# fdcanusb.net
KiCad netlist of a schematic drawn in EAGLE
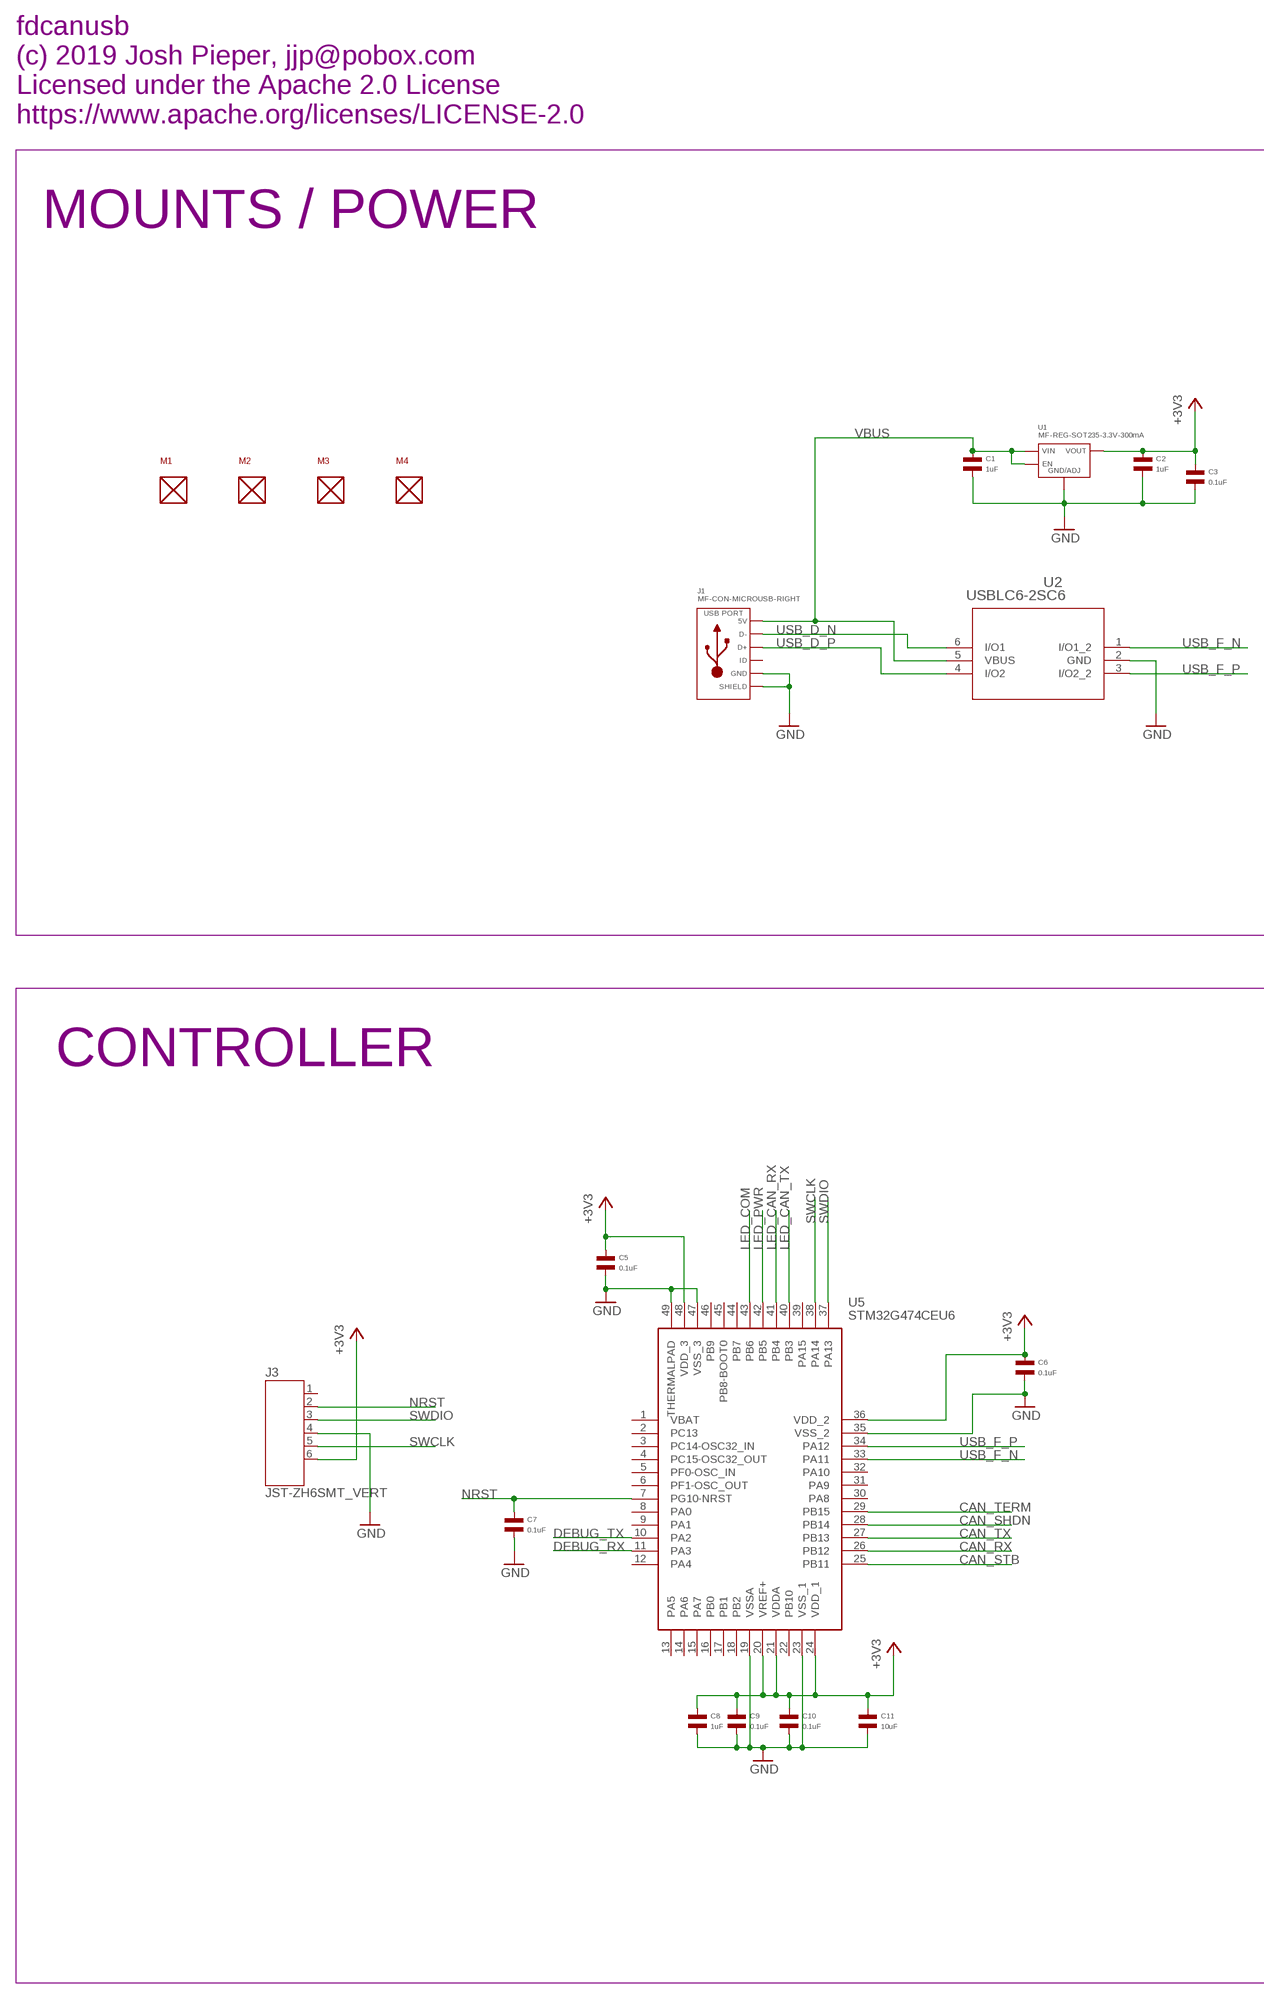
[diagram p0: schematic, sheet 1, part 1 of 2]
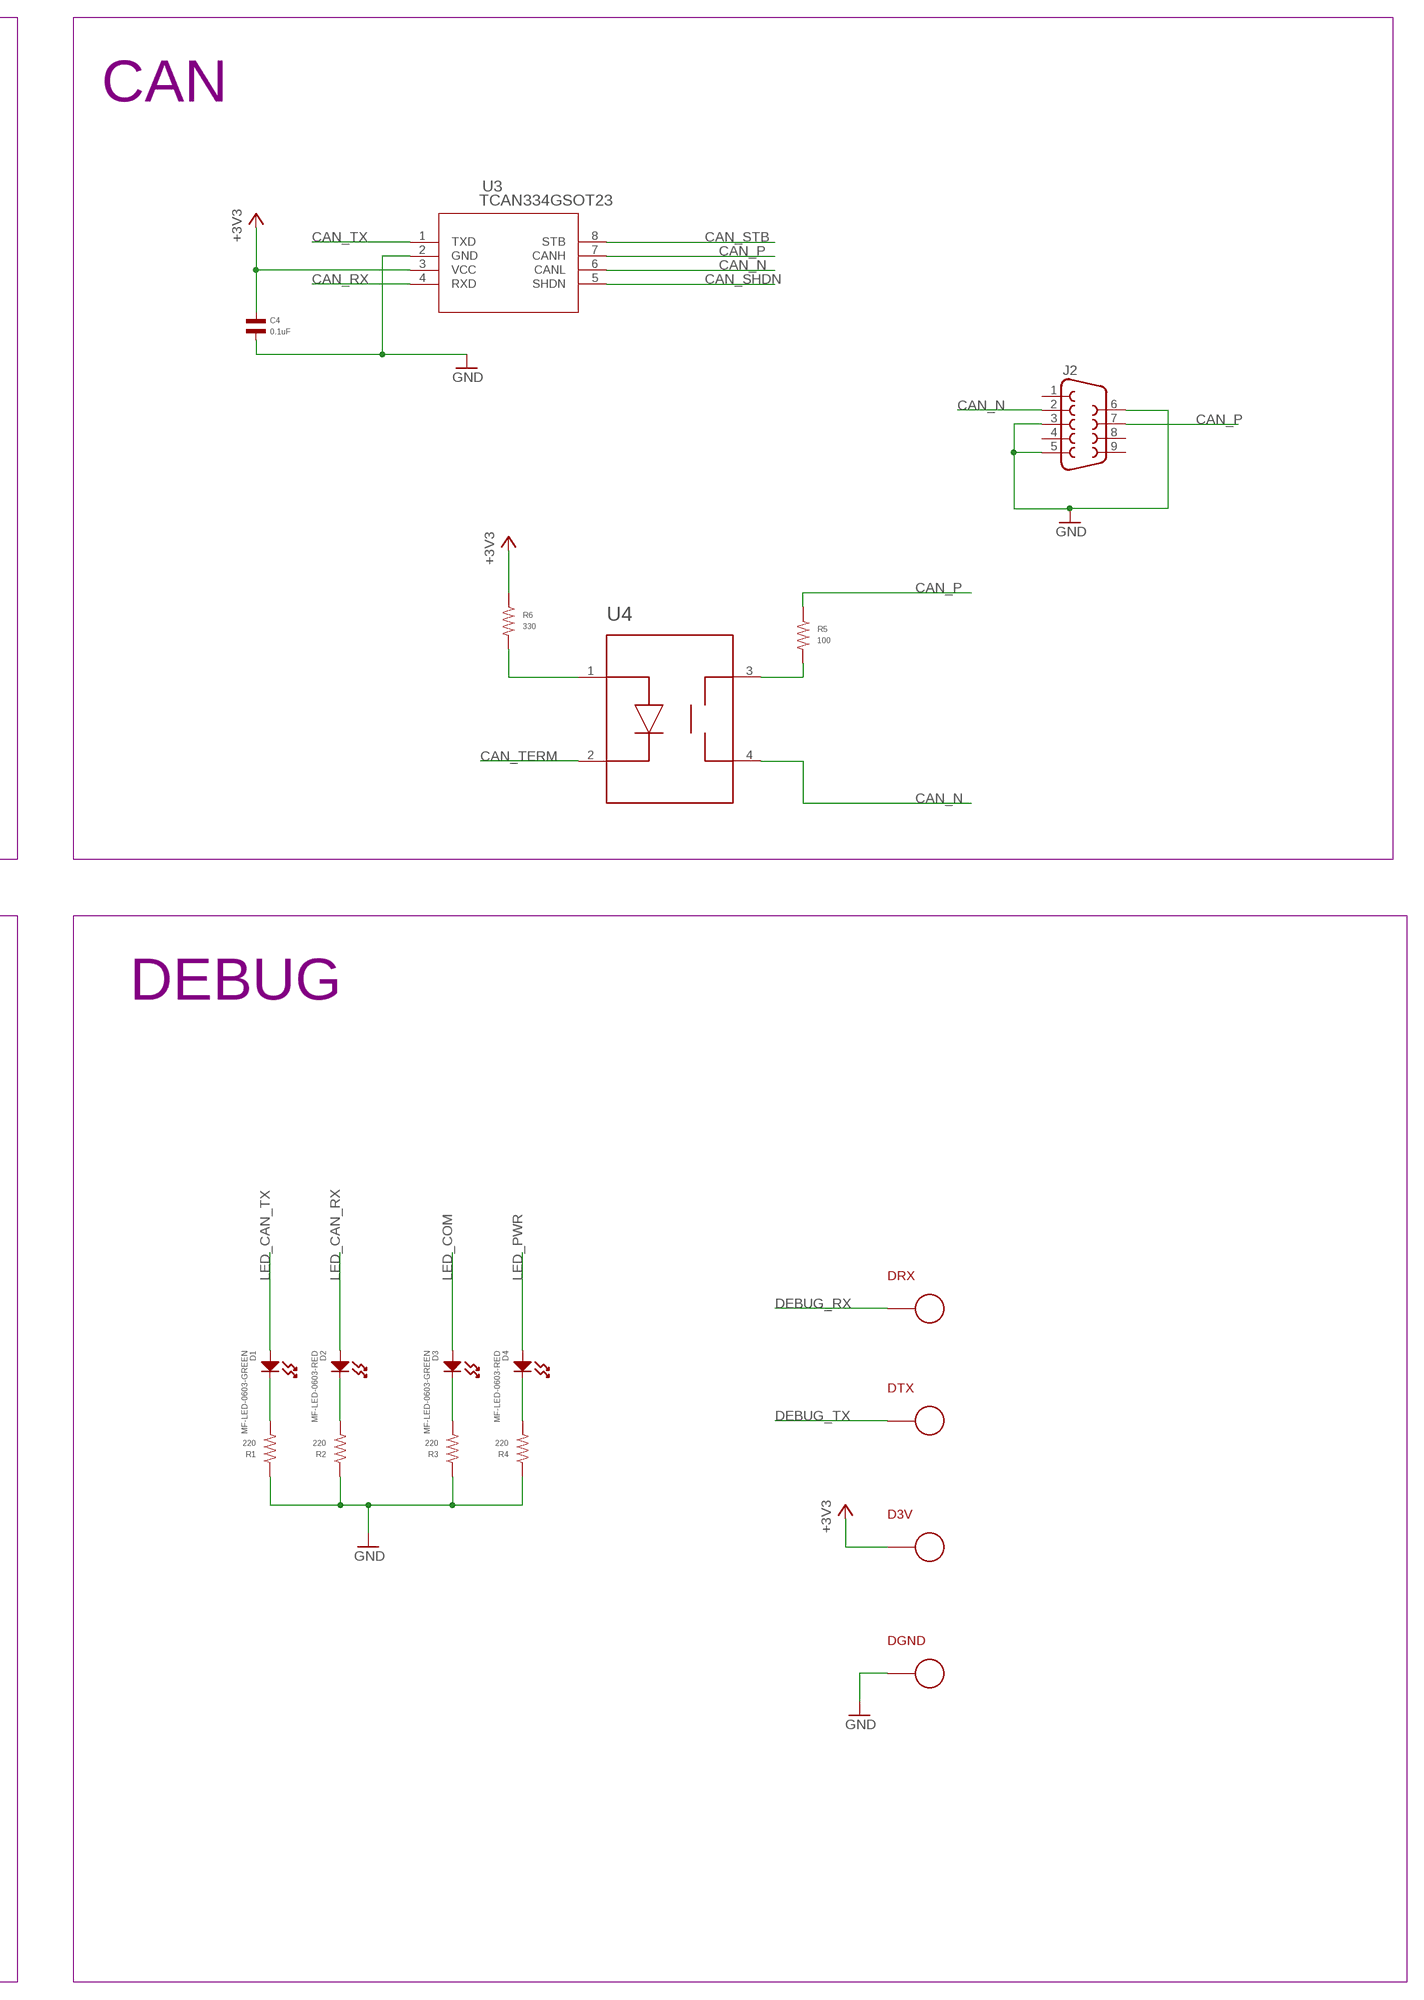
[diagram p1: schematic, sheet 1, part 2 of 2]

(export (version "E")
  (design (tool "Eeschema 10.0.6"))
  (components
    (comp (ref "C1")
      (value "1uF")
      (footprint "eagle-import:C0603")
      (fields (field (name "HOUSEPART") "YES") (field (name "MPN") "MF-CAP-0603-1uF"))
      (libsource (lib "eagle-import") (part "CAPACITOR_NP_0603"))
    )
    (comp (ref "C2")
      (value "1uF")
      (footprint "eagle-import:C0603")
      (fields (field (name "HOUSEPART") "YES") (field (name "MPN") "MF-CAP-0603-1uF"))
      (libsource (lib "eagle-import") (part "CAPACITOR_NP_0603"))
    )
    (comp (ref "C3")
      (value "0.1uF")
      (footprint "eagle-import:C0402")
      (fields (field (name "HOUSEPART") "YES") (field (name "MPN") "MF-CAP-0402-0.1uF"))
      (libsource (lib "eagle-import") (part "CAPACITOR_NP_0402"))
    )
    (comp (ref "C4")
      (value "0.1uF")
      (footprint "eagle-import:C0402")
      (fields (field (name "HOUSEPART") "YES") (field (name "MPN") "MF-CAP-0402-0.1uF"))
      (libsource (lib "eagle-import") (part "CAPACITOR_NP_0402"))
    )
    (comp (ref "C5")
      (value "0.1uF")
      (footprint "eagle-import:C0402")
      (fields (field (name "HOUSEPART") "YES") (field (name "MPN") "MF-CAP-0402-0.1uF"))
      (libsource (lib "eagle-import") (part "CAPACITOR_NP_0402"))
    )
    (comp (ref "C6")
      (value "0.1uF")
      (footprint "eagle-import:C0402")
      (fields (field (name "HOUSEPART") "YES") (field (name "MPN") "MF-CAP-0402-0.1uF"))
      (libsource (lib "eagle-import") (part "CAPACITOR_NP_0402"))
    )
    (comp (ref "C7")
      (value "0.1uF")
      (footprint "eagle-import:C0402")
      (fields (field (name "HOUSEPART") "YES") (field (name "MPN") "MF-CAP-0402-0.1uF"))
      (libsource (lib "eagle-import") (part "CAPACITOR_NP_0402"))
    )
    (comp (ref "C8")
      (value "1uF")
      (footprint "eagle-import:C0603")
      (fields (field (name "HOUSEPART") "YES") (field (name "MPN") "MF-CAP-0603-1uF"))
      (libsource (lib "eagle-import") (part "CAPACITOR_NP_0603"))
    )
    (comp (ref "C9")
      (value "0.1uF")
      (footprint "eagle-import:C0402")
      (fields (field (name "HOUSEPART") "YES") (field (name "MPN") "MF-CAP-0402-0.1uF"))
      (libsource (lib "eagle-import") (part "CAPACITOR_NP_0402"))
    )
    (comp (ref "C10")
      (value "0.1uF")
      (footprint "eagle-import:C0402")
      (fields (field (name "HOUSEPART") "YES") (field (name "MPN") "MF-CAP-0402-0.1uF"))
      (libsource (lib "eagle-import") (part "CAPACITOR_NP_0402"))
    )
    (comp (ref "C11")
      (value "10uF")
      (footprint "eagle-import:C1206")
      (fields (field (name "HOUSEPART") "YES") (field (name "MPN") "MF-CAP-1206-10uF"))
      (libsource (lib "eagle-import") (part "CAPACITOR_NP_1206"))
    )
    (comp (ref "D1")
      (value "MF-LED-0603-GREEN")
      (footprint "eagle-import:LED0603")
      (fields (field (name "HOUSEPART") "YES"))
      (libsource (lib "eagle-import") (part "LED_SINGLE-0603-GREEN"))
    )
    (comp (ref "D2")
      (value "MF-LED-0603-RED")
      (footprint "eagle-import:LED0603")
      (fields (field (name "HOUSEPART") "YES"))
      (libsource (lib "eagle-import") (part "LED_SINGLE-0603-RED"))
    )
    (comp (ref "D3")
      (value "MF-LED-0603-GREEN")
      (footprint "eagle-import:LED0603")
      (fields (field (name "HOUSEPART") "YES"))
      (libsource (lib "eagle-import") (part "LED_SINGLE-0603-GREEN"))
    )
    (comp (ref "D3V")
      (value "PAD24AWG_PAD")
      (footprint "eagle-import:24AWG_PAD")
      (libsource (lib "eagle-import") (part "PAD24AWG_PAD"))
    )
    (comp (ref "D4")
      (value "MF-LED-0603-RED")
      (footprint "eagle-import:LED0603")
      (fields (field (name "HOUSEPART") "YES"))
      (libsource (lib "eagle-import") (part "LED_SINGLE-0603-RED"))
    )
    (comp (ref "DGND")
      (value "PAD24AWG_PAD")
      (footprint "eagle-import:24AWG_PAD")
      (libsource (lib "eagle-import") (part "PAD24AWG_PAD"))
    )
    (comp (ref "DRX")
      (value "PAD24AWG_PAD")
      (footprint "eagle-import:24AWG_PAD")
      (libsource (lib "eagle-import") (part "PAD24AWG_PAD"))
    )
    (comp (ref "DTX")
      (value "PAD24AWG_PAD")
      (footprint "eagle-import:24AWG_PAD")
      (libsource (lib "eagle-import") (part "PAD24AWG_PAD"))
    )
    (comp (ref "J1")
      (value "MF-CON-MICROUSB-RIGHT")
      (footprint "eagle-import:MICROUSB-RIGHT")
      (fields (field (name "HOUSEPART") "YES"))
      (libsource (lib "eagle-import") (part "USB_MICRO_RIGHT"))
    )
    (comp (ref "J2")
      (value "F09H")
      (footprint "eagle-import:F09H")
      (libsource (lib "eagle-import") (part "F09H"))
    )
    (comp (ref "J3")
      (value "JST-ZH6SMT_VERT")
      (footprint "eagle-import:JST_B6B-ZR-SM4-TF(LF)(SN)")
      (fields (field (name "MF") "JST") (field (name "MPN") "B6B-ZR-SM4-TF(LF)(SN)"))
      (libsource (lib "eagle-import") (part "JST-ZH6SMT_VERT"))
    )
    (comp (ref "M1")
      (value "MOUNT")
      (footprint "eagle-import:M2.5MOUNT")
      (libsource (lib "eagle-import") (part "MOUNT"))
    )
    (comp (ref "M2")
      (value "MOUNT")
      (footprint "eagle-import:M2.5MOUNT")
      (libsource (lib "eagle-import") (part "MOUNT"))
    )
    (comp (ref "M3")
      (value "MOUNT")
      (footprint "eagle-import:M2.5MOUNT")
      (libsource (lib "eagle-import") (part "MOUNT"))
    )
    (comp (ref "M4")
      (value "MOUNT")
      (footprint "eagle-import:M2.5MOUNT")
      (libsource (lib "eagle-import") (part "MOUNT"))
    )
    (comp (ref "R1")
      (value "220")
      (footprint "eagle-import:R0402")
      (fields (field (name "MPN") "MF-RES-0402-220"))
      (libsource (lib "eagle-import") (part "RESISTOR_0402"))
    )
    (comp (ref "R2")
      (value "220")
      (footprint "eagle-import:R0402")
      (fields (field (name "MPN") "MF-RES-0402-220"))
      (libsource (lib "eagle-import") (part "RESISTOR_0402"))
    )
    (comp (ref "R3")
      (value "220")
      (footprint "eagle-import:R0402")
      (fields (field (name "MPN") "MF-RES-0402-220"))
      (libsource (lib "eagle-import") (part "RESISTOR_0402"))
    )
    (comp (ref "R4")
      (value "220")
      (footprint "eagle-import:R0402")
      (fields (field (name "MPN") "MF-RES-0402-220"))
      (libsource (lib "eagle-import") (part "RESISTOR_0402"))
    )
    (comp (ref "R5")
      (value "100")
      (footprint "eagle-import:R0805")
      (fields (field (name "MPN") "MF-RES-0805-100"))
      (libsource (lib "eagle-import") (part "RESISTOR_0805"))
    )
    (comp (ref "R6")
      (value "330")
      (footprint "eagle-import:R0402")
      (fields (field (name "MPN") "MF-RES-0402-330"))
      (libsource (lib "eagle-import") (part "RESISTOR_0402"))
    )
    (comp (ref "U1")
      (value "MF-REG-SOT235-3.3V-300mA")
      (footprint "eagle-import:SOT-23-5")
      (fields (field (name "HOUSEPART") "YES"))
      (libsource (lib "eagle-import") (part "TLV70233PDBVR"))
    )
    (comp (ref "U2")
      (value "USBLC6-2SC6")
      (footprint "eagle-import:SOT23-6L")
      (fields (field (name "MANUFACTURER_PART_NUMBER") "USBLC62SC6") (field (name "MF") "ST"))
      (libsource (lib "eagle-import") (part "USBLC6-2SC6"))
    )
    (comp (ref "U3")
      (value "TCAN334GSOT23")
      (footprint "eagle-import:SOT23-8")
      (fields (field (name "MF") "TI") (field (name "MPN") "TCAN334GDCNT"))
      (libsource (lib "eagle-import") (part "TCAN334GSOT23"))
    )
    (comp (ref "U4")
      (value "TLP3317")
      (footprint "eagle-import:TLP3317")
      (fields
        (field (name "MF") "TOSHIBA")
        (field (name "MPN") "TLP3317(TP15,F")
        (field (name "MPN_1") "TLP3317")
      )
      (libsource (lib "eagle-import") (part "TLP3317"))
    )
    (comp (ref "U5")
      (value "STM32G474CEU6")
      (footprint "eagle-import:QFN50P700X700X60-49N")
      (fields (field (name "MOUSER_PART_NUMBER") "511-STM32G474CEU6") (field (name "MF") "ST"))
      (libsource (lib "eagle-import") (part "STM32G474CEU6"))
    )
  )
  (nets
    (net (code "1") (name "+3V3") (class "Default")
      (node (ref "C10") (pin "P$1") (pinfunction "P$1_P$1") (pintype "passive"))
      (node (ref "C11") (pin "P$1") (pinfunction "P$1_P$1") (pintype "passive"))
      (node (ref "C2") (pin "P$1") (pinfunction "P$1_P$1") (pintype "passive"))
      (node (ref "C3") (pin "P$1") (pinfunction "P$1_P$1") (pintype "passive"))
      (node (ref "C4") (pin "P$1") (pinfunction "P$1_P$1") (pintype "passive"))
      (node (ref "C5") (pin "P$1") (pinfunction "P$1_P$1") (pintype "passive"))
      (node (ref "C6") (pin "P$1") (pinfunction "P$1_P$1") (pintype "passive"))
      (node (ref "C8") (pin "P$1") (pinfunction "P$1_P$1") (pintype "passive"))
      (node (ref "C9") (pin "P$1") (pinfunction "P$1_P$1") (pintype "passive"))
      (node (ref "D3V") (pin "P$1") (pinfunction "P$1_P$1") (pintype "bidirectional"))
      (node (ref "J3") (pin "6") (pinfunction "6_6") (pintype "passive"))
      (node (ref "R6") (pin "P$1") (pinfunction "P$1_P$1") (pintype "passive"))
      (node (ref "U1") (pin "P$5") (pinfunction "VOUT_P$5") (pintype "bidirectional"))
      (node (ref "U3") (pin "3") (pinfunction "VCC_3") (pintype "power_in"))
      (node (ref "U5") (pin "20") (pinfunction "VREF+_20") (pintype "bidirectional"))
      (node (ref "U5") (pin "21") (pinfunction "VDDA_21") (pintype "bidirectional"))
      (node (ref "U5") (pin "24") (pinfunction "VDD_1_24") (pintype "bidirectional"))
      (node (ref "U5") (pin "36") (pinfunction "VDD_2_36") (pintype "bidirectional"))
      (node (ref "U5") (pin "48") (pinfunction "VDD_3_48") (pintype "bidirectional"))
    )
    (net (code "2") (name "/CAN_N") (class "Default")
      (node (ref "J2") (pin "2") (pinfunction "2_2") (pintype "passive"))
      (node (ref "U3") (pin "6") (pinfunction "CANL_6") (pintype "bidirectional"))
      (node (ref "U4") (pin "4") (pinfunction "SW2_4") (pintype "bidirectional"))
    )
    (net (code "3") (name "/CAN_P") (class "Default")
      (node (ref "J2") (pin "7") (pinfunction "7_7") (pintype "passive"))
      (node (ref "R5") (pin "P$1") (pinfunction "P$1_P$1") (pintype "passive"))
      (node (ref "U3") (pin "7") (pinfunction "CANH_7") (pintype "bidirectional"))
    )
    (net (code "4") (name "/CAN_RX") (class "Default")
      (node (ref "U3") (pin "4") (pinfunction "RXD_4") (pintype "output"))
      (node (ref "U5") (pin "26") (pinfunction "PB12_26") (pintype "bidirectional"))
    )
    (net (code "5") (name "/CAN_SHDN") (class "Default")
      (node (ref "U3") (pin "5") (pinfunction "SHDN_5") (pintype "input"))
      (node (ref "U5") (pin "28") (pinfunction "PB14_28") (pintype "bidirectional"))
    )
    (net (code "6") (name "/CAN_STB") (class "Default")
      (node (ref "U3") (pin "8") (pinfunction "STB_8") (pintype "input"))
      (node (ref "U5") (pin "25") (pinfunction "PB11_25") (pintype "bidirectional"))
    )
    (net (code "7") (name "/CAN_TERM") (class "Default")
      (node (ref "U4") (pin "2") (pinfunction "CATHODE_2") (pintype "bidirectional"))
      (node (ref "U5") (pin "29") (pinfunction "PB15_29") (pintype "bidirectional"))
    )
    (net (code "8") (name "/CAN_TX") (class "Default")
      (node (ref "U3") (pin "1") (pinfunction "TXD_1") (pintype "input"))
      (node (ref "U5") (pin "27") (pinfunction "PB13_27") (pintype "bidirectional"))
    )
    (net (code "9") (name "/DEBUG_RX") (class "Default")
      (node (ref "DRX") (pin "P$1") (pinfunction "P$1_P$1") (pintype "bidirectional"))
      (node (ref "U5") (pin "11") (pinfunction "PA3_11") (pintype "bidirectional"))
    )
    (net (code "10") (name "/DEBUG_TX") (class "Default")
      (node (ref "DTX") (pin "P$1") (pinfunction "P$1_P$1") (pintype "bidirectional"))
      (node (ref "U5") (pin "10") (pinfunction "PA2_10") (pintype "bidirectional"))
    )
    (net (code "11") (name "/LED_CAN_RX") (class "Default")
      (node (ref "D2") (pin "ANODE") (pinfunction "ANODE_ANODE") (pintype "power_in"))
      (node (ref "U5") (pin "41") (pinfunction "PB4_41") (pintype "bidirectional"))
    )
    (net (code "12") (name "/LED_CAN_TX") (class "Default")
      (node (ref "D1") (pin "ANODE") (pinfunction "ANODE_ANODE") (pintype "power_in"))
      (node (ref "U5") (pin "40") (pinfunction "PB3_40") (pintype "bidirectional"))
    )
    (net (code "13") (name "/LED_COM") (class "Default")
      (node (ref "D3") (pin "ANODE") (pinfunction "ANODE_ANODE") (pintype "power_in"))
      (node (ref "U5") (pin "43") (pinfunction "PB6_43") (pintype "bidirectional"))
    )
    (net (code "14") (name "/LED_PWR") (class "Default")
      (node (ref "D4") (pin "ANODE") (pinfunction "ANODE_ANODE") (pintype "power_in"))
      (node (ref "U5") (pin "42") (pinfunction "PB5_42") (pintype "bidirectional"))
    )
    (net (code "15") (name "/NRST") (class "Default")
      (node (ref "C7") (pin "P$1") (pinfunction "P$1_P$1") (pintype "passive"))
      (node (ref "J3") (pin "2") (pinfunction "2_2") (pintype "passive"))
      (node (ref "U5") (pin "7") (pinfunction "PG10-NRST_7") (pintype "bidirectional"))
    )
    (net (code "16") (name "/SWCLK") (class "Default")
      (node (ref "J3") (pin "5") (pinfunction "5_5") (pintype "passive"))
      (node (ref "U5") (pin "38") (pinfunction "PA14_38") (pintype "bidirectional"))
    )
    (net (code "17") (name "/SWDIO") (class "Default")
      (node (ref "J3") (pin "3") (pinfunction "3_3") (pintype "passive"))
      (node (ref "U5") (pin "37") (pinfunction "PA13_37") (pintype "bidirectional"))
    )
    (net (code "18") (name "/USB_D_N") (class "Default")
      (node (ref "J1") (pin "2") (pinfunction "D-_2") (pintype "bidirectional"))
      (node (ref "U2") (pin "6") (pinfunction "I/O1_6") (pintype "bidirectional"))
    )
    (net (code "19") (name "/USB_D_P") (class "Default")
      (node (ref "J1") (pin "3") (pinfunction "D+_3") (pintype "bidirectional"))
      (node (ref "U2") (pin "4") (pinfunction "I/O2_4") (pintype "bidirectional"))
    )
    (net (code "20") (name "/USB_F_N") (class "Default")
      (node (ref "U2") (pin "1") (pinfunction "I/O1_2_1") (pintype "bidirectional"))
      (node (ref "U5") (pin "33") (pinfunction "PA11_33") (pintype "bidirectional"))
    )
    (net (code "21") (name "/USB_F_P") (class "Default")
      (node (ref "U2") (pin "3") (pinfunction "I/O2_2_3") (pintype "bidirectional"))
      (node (ref "U5") (pin "34") (pinfunction "PA12_34") (pintype "bidirectional"))
    )
    (net (code "22") (name "/VBUS") (class "Default")
      (node (ref "C1") (pin "P$1") (pinfunction "P$1_P$1") (pintype "passive"))
      (node (ref "J1") (pin "1") (pinfunction "5V_1") (pintype "power_in"))
      (node (ref "U1") (pin "P$1") (pinfunction "VIN_P$1") (pintype "bidirectional"))
      (node (ref "U1") (pin "P$3") (pinfunction "EN_P$3") (pintype "bidirectional"))
      (node (ref "U2") (pin "5") (pinfunction "VBUS_5") (pintype "power_in"))
    )
    (net (code "23") (name "GND") (class "Default")
      (node (ref "C1") (pin "P$2") (pinfunction "P$2_P$2") (pintype "passive"))
      (node (ref "C10") (pin "P$2") (pinfunction "P$2_P$2") (pintype "passive"))
      (node (ref "C11") (pin "P$2") (pinfunction "P$2_P$2") (pintype "passive"))
      (node (ref "C2") (pin "P$2") (pinfunction "P$2_P$2") (pintype "passive"))
      (node (ref "C3") (pin "P$2") (pinfunction "P$2_P$2") (pintype "passive"))
      (node (ref "C4") (pin "P$2") (pinfunction "P$2_P$2") (pintype "passive"))
      (node (ref "C5") (pin "P$2") (pinfunction "P$2_P$2") (pintype "passive"))
      (node (ref "C6") (pin "P$2") (pinfunction "P$2_P$2") (pintype "passive"))
      (node (ref "C7") (pin "P$2") (pinfunction "P$2_P$2") (pintype "passive"))
      (node (ref "C8") (pin "P$2") (pinfunction "P$2_P$2") (pintype "passive"))
      (node (ref "C9") (pin "P$2") (pinfunction "P$2_P$2") (pintype "passive"))
      (node (ref "DGND") (pin "P$1") (pinfunction "P$1_P$1") (pintype "bidirectional"))
      (node (ref "J1") (pin "5") (pinfunction "GND_5") (pintype "power_in"))
      (node (ref "J1") (pin "S1") (pinfunction "SLD_S1") (pintype "power_in"))
      (node (ref "J1") (pin "S2") (pinfunction "SLD_S2") (pintype "power_in"))
      (node (ref "J1") (pin "S3") (pinfunction "SLD_S3") (pintype "power_in"))
      (node (ref "J1") (pin "S4") (pinfunction "SLD_S4") (pintype "power_in"))
      (node (ref "J1") (pin "S5") (pinfunction "SLD_S5") (pintype "power_in"))
      (node (ref "J1") (pin "S6") (pinfunction "SLD_S6") (pintype "power_in"))
      (node (ref "J2") (pin "3") (pinfunction "3_3") (pintype "passive"))
      (node (ref "J2") (pin "5") (pinfunction "5_5") (pintype "passive"))
      (node (ref "J2") (pin "6") (pinfunction "6_6") (pintype "passive"))
      (node (ref "J3") (pin "4") (pinfunction "4_4") (pintype "passive"))
      (node (ref "R1") (pin "P$1") (pinfunction "P$1_P$1") (pintype "passive"))
      (node (ref "R2") (pin "P$1") (pinfunction "P$1_P$1") (pintype "passive"))
      (node (ref "R3") (pin "P$1") (pinfunction "P$1_P$1") (pintype "passive"))
      (node (ref "R4") (pin "P$1") (pinfunction "P$1_P$1") (pintype "passive"))
      (node (ref "U1") (pin "P$2") (pinfunction "GND/ADJ_P$2") (pintype "bidirectional"))
      (node (ref "U2") (pin "2") (pinfunction "GND_2") (pintype "power_in"))
      (node (ref "U3") (pin "2") (pinfunction "GND_2") (pintype "power_in"))
      (node (ref "U5") (pin "19") (pinfunction "VSSA_19") (pintype "bidirectional"))
      (node (ref "U5") (pin "23") (pinfunction "VSS_1_23") (pintype "bidirectional"))
      (node (ref "U5") (pin "35") (pinfunction "VSS_2_35") (pintype "bidirectional"))
      (node (ref "U5") (pin "47") (pinfunction "VSS_3_47") (pintype "bidirectional"))
      (node (ref "U5") (pin "49") (pinfunction "THERMALPAD_49") (pintype "bidirectional"))
    )
    (net (code "24") (name "Net-(D1-PadCATHODE)") (class "Default")
      (node (ref "D1") (pin "CATHODE") (pinfunction "CATHODE_CATHODE") (pintype "power_in"))
      (node (ref "R1") (pin "P$2") (pinfunction "P$2_P$2") (pintype "passive"))
    )
    (net (code "25") (name "Net-(D2-PadCATHODE)") (class "Default")
      (node (ref "D2") (pin "CATHODE") (pinfunction "CATHODE_CATHODE") (pintype "power_in"))
      (node (ref "R2") (pin "P$2") (pinfunction "P$2_P$2") (pintype "passive"))
    )
    (net (code "26") (name "Net-(D3-PadCATHODE)") (class "Default")
      (node (ref "D3") (pin "CATHODE") (pinfunction "CATHODE_CATHODE") (pintype "power_in"))
      (node (ref "R3") (pin "P$2") (pinfunction "P$2_P$2") (pintype "passive"))
    )
    (net (code "27") (name "Net-(D4-PadCATHODE)") (class "Default")
      (node (ref "D4") (pin "CATHODE") (pinfunction "CATHODE_CATHODE") (pintype "power_in"))
      (node (ref "R4") (pin "P$2") (pinfunction "P$2_P$2") (pintype "passive"))
    )
    (net (code "28") (name "Net-(U4-ANODE)") (class "Default")
      (node (ref "R6") (pin "P$2") (pinfunction "P$2_P$2") (pintype "passive"))
      (node (ref "U4") (pin "1") (pinfunction "ANODE_1") (pintype "bidirectional"))
    )
    (net (code "29") (name "Net-(U4-SW1)") (class "Default")
      (node (ref "R5") (pin "P$2") (pinfunction "P$2_P$2") (pintype "passive"))
      (node (ref "U4") (pin "3") (pinfunction "SW1_3") (pintype "bidirectional"))
    )
    (net (code "30") (name "unconnected-(J1-ID-Pad4)") (class "Default")
      (node (ref "J1") (pin "4") (pinfunction "ID_4") (pintype "bidirectional"))
    )
    (net (code "31") (name "unconnected-(J2-Pad1)") (class "Default")
      (node (ref "J2") (pin "1") (pinfunction "1_1") (pintype "passive"))
    )
    (net (code "32") (name "unconnected-(J2-Pad4)") (class "Default")
      (node (ref "J2") (pin "4") (pinfunction "4_4") (pintype "passive"))
    )
    (net (code "33") (name "unconnected-(J2-Pad8)") (class "Default")
      (node (ref "J2") (pin "8") (pinfunction "8_8") (pintype "passive"))
    )
    (net (code "34") (name "unconnected-(J2-Pad9)") (class "Default")
      (node (ref "J2") (pin "9") (pinfunction "9_9") (pintype "passive"))
    )
    (net (code "35") (name "unconnected-(J3-Pad1)") (class "Default")
      (node (ref "J3") (pin "1") (pinfunction "1_1") (pintype "passive"))
    )
    (net (code "36") (name "unconnected-(U5-PA0-Pad8)") (class "Default")
      (node (ref "U5") (pin "8") (pinfunction "PA0_8") (pintype "bidirectional"))
    )
    (net (code "37") (name "unconnected-(U5-PA1-Pad9)") (class "Default")
      (node (ref "U5") (pin "9") (pinfunction "PA1_9") (pintype "bidirectional"))
    )
    (net (code "38") (name "unconnected-(U5-PA4-Pad12)") (class "Default")
      (node (ref "U5") (pin "12") (pinfunction "PA4_12") (pintype "bidirectional"))
    )
    (net (code "39") (name "unconnected-(U5-PA5-Pad13)") (class "Default")
      (node (ref "U5") (pin "13") (pinfunction "PA5_13") (pintype "bidirectional"))
    )
    (net (code "40") (name "unconnected-(U5-PA6-Pad14)") (class "Default")
      (node (ref "U5") (pin "14") (pinfunction "PA6_14") (pintype "bidirectional"))
    )
    (net (code "41") (name "unconnected-(U5-PA7-Pad15)") (class "Default")
      (node (ref "U5") (pin "15") (pinfunction "PA7_15") (pintype "bidirectional"))
    )
    (net (code "42") (name "unconnected-(U5-PA8-Pad30)") (class "Default")
      (node (ref "U5") (pin "30") (pinfunction "PA8_30") (pintype "bidirectional"))
    )
    (net (code "43") (name "unconnected-(U5-PA9-Pad31)") (class "Default")
      (node (ref "U5") (pin "31") (pinfunction "PA9_31") (pintype "bidirectional"))
    )
    (net (code "44") (name "unconnected-(U5-PA10-Pad32)") (class "Default")
      (node (ref "U5") (pin "32") (pinfunction "PA10_32") (pintype "bidirectional"))
    )
    (net (code "45") (name "unconnected-(U5-PA15-Pad39)") (class "Default")
      (node (ref "U5") (pin "39") (pinfunction "PA15_39") (pintype "bidirectional"))
    )
    (net (code "46") (name "unconnected-(U5-PB0-Pad16)") (class "Default")
      (node (ref "U5") (pin "16") (pinfunction "PB0_16") (pintype "bidirectional"))
    )
    (net (code "47") (name "unconnected-(U5-PB1-Pad17)") (class "Default")
      (node (ref "U5") (pin "17") (pinfunction "PB1_17") (pintype "bidirectional"))
    )
    (net (code "48") (name "unconnected-(U5-PB2-Pad18)") (class "Default")
      (node (ref "U5") (pin "18") (pinfunction "PB2_18") (pintype "bidirectional"))
    )
    (net (code "49") (name "unconnected-(U5-PB7-Pad44)") (class "Default")
      (node (ref "U5") (pin "44") (pinfunction "PB7_44") (pintype "bidirectional"))
    )
    (net (code "50") (name "unconnected-(U5-PB8-BOOT0-Pad45)") (class "Default")
      (node (ref "U5") (pin "45") (pinfunction "PB8-BOOT0_45") (pintype "bidirectional"))
    )
    (net (code "51") (name "unconnected-(U5-PB9-Pad46)") (class "Default")
      (node (ref "U5") (pin "46") (pinfunction "PB9_46") (pintype "bidirectional"))
    )
    (net (code "52") (name "unconnected-(U5-PB10-Pad22)") (class "Default")
      (node (ref "U5") (pin "22") (pinfunction "PB10_22") (pintype "bidirectional"))
    )
    (net (code "53") (name "unconnected-(U5-PC13-Pad2)") (class "Default")
      (node (ref "U5") (pin "2") (pinfunction "PC13_2") (pintype "bidirectional"))
    )
    (net (code "54") (name "unconnected-(U5-PC14-OSC32_IN-Pad3)") (class "Default")
      (node (ref "U5") (pin "3") (pinfunction "PC14-OSC32_IN_3") (pintype "bidirectional"))
    )
    (net (code "55") (name "unconnected-(U5-PC15-OSC32_OUT-Pad4)") (class "Default")
      (node (ref "U5") (pin "4") (pinfunction "PC15-OSC32_OUT_4") (pintype "bidirectional"))
    )
    (net (code "56") (name "unconnected-(U5-PF0-OSC_IN-Pad5)") (class "Default")
      (node (ref "U5") (pin "5") (pinfunction "PF0-OSC_IN_5") (pintype "bidirectional"))
    )
    (net (code "57") (name "unconnected-(U5-PF1-OSC_OUT-Pad6)") (class "Default")
      (node (ref "U5") (pin "6") (pinfunction "PF1-OSC_OUT_6") (pintype "bidirectional"))
    )
    (net (code "58") (name "unconnected-(U5-VBAT-Pad1)") (class "Default")
      (node (ref "U5") (pin "1") (pinfunction "VBAT_1") (pintype "bidirectional"))
    )
  )
)
